# SubBus6.net
KiCad netlist of a schematic drawn in Altium Designer
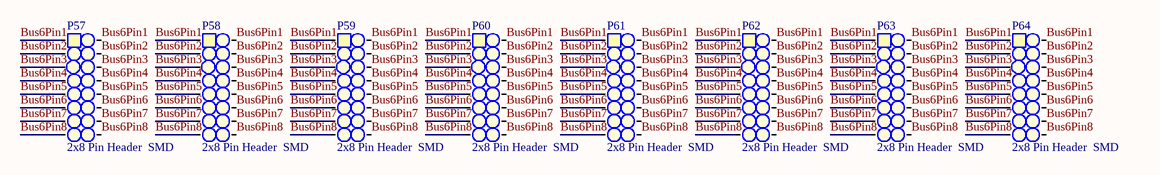
[diagram p0: SubBus6.SchDoc]

(export (version "E")
  (design (tool "Eeschema 10.0.6"))
  (components
    (comp (ref "P57")
      (value "2x8 Pin Header  SMD")
      (footprint "2X8_SMD_PH_2.54")
      (description "2.54mm, SMD")
      (libsource (lib "jclib") (part "2x8 Pin Header  SMD"))
    )
    (comp (ref "P58")
      (value "2x8 Pin Header  SMD")
      (footprint "2X8_SMD_PH_2.54")
      (description "2.54mm, SMD")
      (libsource (lib "jclib") (part "2x8 Pin Header  SMD"))
    )
    (comp (ref "P59")
      (value "2x8 Pin Header  SMD")
      (footprint "2X8_SMD_PH_2.54")
      (description "2.54mm, SMD")
      (libsource (lib "jclib") (part "2x8 Pin Header  SMD"))
    )
    (comp (ref "P60")
      (value "2x8 Pin Header  SMD")
      (footprint "2X8_SMD_PH_2.54")
      (description "2.54mm, SMD")
      (libsource (lib "jclib") (part "2x8 Pin Header  SMD"))
    )
    (comp (ref "P61")
      (value "2x8 Pin Header  SMD")
      (footprint "2X8_SMD_PH_2.54")
      (description "2.54mm, SMD")
      (libsource (lib "jclib") (part "2x8 Pin Header  SMD"))
    )
    (comp (ref "P62")
      (value "2x8 Pin Header  SMD")
      (footprint "2X8_SMD_PH_2.54")
      (description "2.54mm, SMD")
      (libsource (lib "jclib") (part "2x8 Pin Header  SMD"))
    )
    (comp (ref "P63")
      (value "2x8 Pin Header  SMD")
      (footprint "2X8_SMD_PH_2.54")
      (description "2.54mm, SMD")
      (libsource (lib "jclib") (part "2x8 Pin Header  SMD"))
    )
    (comp (ref "P64")
      (value "2x8 Pin Header  SMD")
      (footprint "2X8_SMD_PH_2.54")
      (description "2.54mm, SMD")
      (libsource (lib "jclib") (part "2x8 Pin Header  SMD"))
    )
  )
  (nets
    (net (code "1") (name "/Bus6Pin1") (class "Default")
      (node (ref "P57") (pin "1") (pinfunction "1_1") (pintype "passive"))
      (node (ref "P57") (pin "16") (pinfunction "16_16") (pintype "passive"))
      (node (ref "P58") (pin "1") (pinfunction "1_1") (pintype "passive"))
      (node (ref "P58") (pin "16") (pinfunction "16_16") (pintype "passive"))
      (node (ref "P59") (pin "1") (pinfunction "1_1") (pintype "passive"))
      (node (ref "P59") (pin "16") (pinfunction "16_16") (pintype "passive"))
      (node (ref "P60") (pin "1") (pinfunction "1_1") (pintype "passive"))
      (node (ref "P60") (pin "16") (pinfunction "16_16") (pintype "passive"))
      (node (ref "P61") (pin "1") (pinfunction "1_1") (pintype "passive"))
      (node (ref "P61") (pin "16") (pinfunction "16_16") (pintype "passive"))
      (node (ref "P62") (pin "1") (pinfunction "1_1") (pintype "passive"))
      (node (ref "P62") (pin "16") (pinfunction "16_16") (pintype "passive"))
      (node (ref "P63") (pin "1") (pinfunction "1_1") (pintype "passive"))
      (node (ref "P63") (pin "16") (pinfunction "16_16") (pintype "passive"))
      (node (ref "P64") (pin "1") (pinfunction "1_1") (pintype "passive"))
      (node (ref "P64") (pin "16") (pinfunction "16_16") (pintype "passive"))
    )
    (net (code "2") (name "/Bus6Pin2") (class "Default")
      (node (ref "P57") (pin "15") (pinfunction "15_15") (pintype "passive"))
      (node (ref "P57") (pin "2") (pinfunction "2_2") (pintype "passive"))
      (node (ref "P58") (pin "15") (pinfunction "15_15") (pintype "passive"))
      (node (ref "P58") (pin "2") (pinfunction "2_2") (pintype "passive"))
      (node (ref "P59") (pin "15") (pinfunction "15_15") (pintype "passive"))
      (node (ref "P59") (pin "2") (pinfunction "2_2") (pintype "passive"))
      (node (ref "P60") (pin "15") (pinfunction "15_15") (pintype "passive"))
      (node (ref "P60") (pin "2") (pinfunction "2_2") (pintype "passive"))
      (node (ref "P61") (pin "15") (pinfunction "15_15") (pintype "passive"))
      (node (ref "P61") (pin "2") (pinfunction "2_2") (pintype "passive"))
      (node (ref "P62") (pin "15") (pinfunction "15_15") (pintype "passive"))
      (node (ref "P62") (pin "2") (pinfunction "2_2") (pintype "passive"))
      (node (ref "P63") (pin "15") (pinfunction "15_15") (pintype "passive"))
      (node (ref "P63") (pin "2") (pinfunction "2_2") (pintype "passive"))
      (node (ref "P64") (pin "15") (pinfunction "15_15") (pintype "passive"))
      (node (ref "P64") (pin "2") (pinfunction "2_2") (pintype "passive"))
    )
    (net (code "3") (name "/Bus6Pin3") (class "Default")
      (node (ref "P57") (pin "14") (pinfunction "14_14") (pintype "passive"))
      (node (ref "P57") (pin "3") (pinfunction "3_3") (pintype "passive"))
      (node (ref "P58") (pin "14") (pinfunction "14_14") (pintype "passive"))
      (node (ref "P58") (pin "3") (pinfunction "3_3") (pintype "passive"))
      (node (ref "P59") (pin "14") (pinfunction "14_14") (pintype "passive"))
      (node (ref "P59") (pin "3") (pinfunction "3_3") (pintype "passive"))
      (node (ref "P60") (pin "14") (pinfunction "14_14") (pintype "passive"))
      (node (ref "P60") (pin "3") (pinfunction "3_3") (pintype "passive"))
      (node (ref "P61") (pin "14") (pinfunction "14_14") (pintype "passive"))
      (node (ref "P61") (pin "3") (pinfunction "3_3") (pintype "passive"))
      (node (ref "P62") (pin "14") (pinfunction "14_14") (pintype "passive"))
      (node (ref "P62") (pin "3") (pinfunction "3_3") (pintype "passive"))
      (node (ref "P63") (pin "14") (pinfunction "14_14") (pintype "passive"))
      (node (ref "P63") (pin "3") (pinfunction "3_3") (pintype "passive"))
      (node (ref "P64") (pin "14") (pinfunction "14_14") (pintype "passive"))
      (node (ref "P64") (pin "3") (pinfunction "3_3") (pintype "passive"))
    )
    (net (code "4") (name "/Bus6Pin4") (class "Default")
      (node (ref "P57") (pin "13") (pinfunction "13_13") (pintype "passive"))
      (node (ref "P57") (pin "4") (pinfunction "4_4") (pintype "passive"))
      (node (ref "P58") (pin "13") (pinfunction "13_13") (pintype "passive"))
      (node (ref "P58") (pin "4") (pinfunction "4_4") (pintype "passive"))
      (node (ref "P59") (pin "13") (pinfunction "13_13") (pintype "passive"))
      (node (ref "P59") (pin "4") (pinfunction "4_4") (pintype "passive"))
      (node (ref "P60") (pin "13") (pinfunction "13_13") (pintype "passive"))
      (node (ref "P60") (pin "4") (pinfunction "4_4") (pintype "passive"))
      (node (ref "P61") (pin "13") (pinfunction "13_13") (pintype "passive"))
      (node (ref "P61") (pin "4") (pinfunction "4_4") (pintype "passive"))
      (node (ref "P62") (pin "13") (pinfunction "13_13") (pintype "passive"))
      (node (ref "P62") (pin "4") (pinfunction "4_4") (pintype "passive"))
      (node (ref "P63") (pin "13") (pinfunction "13_13") (pintype "passive"))
      (node (ref "P63") (pin "4") (pinfunction "4_4") (pintype "passive"))
      (node (ref "P64") (pin "13") (pinfunction "13_13") (pintype "passive"))
      (node (ref "P64") (pin "4") (pinfunction "4_4") (pintype "passive"))
    )
    (net (code "5") (name "/Bus6Pin5") (class "Default")
      (node (ref "P57") (pin "12") (pinfunction "12_12") (pintype "passive"))
      (node (ref "P57") (pin "5") (pinfunction "5_5") (pintype "passive"))
      (node (ref "P58") (pin "12") (pinfunction "12_12") (pintype "passive"))
      (node (ref "P58") (pin "5") (pinfunction "5_5") (pintype "passive"))
      (node (ref "P59") (pin "12") (pinfunction "12_12") (pintype "passive"))
      (node (ref "P59") (pin "5") (pinfunction "5_5") (pintype "passive"))
      (node (ref "P60") (pin "12") (pinfunction "12_12") (pintype "passive"))
      (node (ref "P60") (pin "5") (pinfunction "5_5") (pintype "passive"))
      (node (ref "P61") (pin "12") (pinfunction "12_12") (pintype "passive"))
      (node (ref "P61") (pin "5") (pinfunction "5_5") (pintype "passive"))
      (node (ref "P62") (pin "12") (pinfunction "12_12") (pintype "passive"))
      (node (ref "P62") (pin "5") (pinfunction "5_5") (pintype "passive"))
      (node (ref "P63") (pin "12") (pinfunction "12_12") (pintype "passive"))
      (node (ref "P63") (pin "5") (pinfunction "5_5") (pintype "passive"))
      (node (ref "P64") (pin "12") (pinfunction "12_12") (pintype "passive"))
      (node (ref "P64") (pin "5") (pinfunction "5_5") (pintype "passive"))
    )
    (net (code "6") (name "/Bus6Pin6") (class "Default")
      (node (ref "P57") (pin "11") (pinfunction "11_11") (pintype "passive"))
      (node (ref "P57") (pin "6") (pinfunction "6_6") (pintype "passive"))
      (node (ref "P58") (pin "11") (pinfunction "11_11") (pintype "passive"))
      (node (ref "P58") (pin "6") (pinfunction "6_6") (pintype "passive"))
      (node (ref "P59") (pin "11") (pinfunction "11_11") (pintype "passive"))
      (node (ref "P59") (pin "6") (pinfunction "6_6") (pintype "passive"))
      (node (ref "P60") (pin "11") (pinfunction "11_11") (pintype "passive"))
      (node (ref "P60") (pin "6") (pinfunction "6_6") (pintype "passive"))
      (node (ref "P61") (pin "11") (pinfunction "11_11") (pintype "passive"))
      (node (ref "P61") (pin "6") (pinfunction "6_6") (pintype "passive"))
      (node (ref "P62") (pin "11") (pinfunction "11_11") (pintype "passive"))
      (node (ref "P62") (pin "6") (pinfunction "6_6") (pintype "passive"))
      (node (ref "P63") (pin "11") (pinfunction "11_11") (pintype "passive"))
      (node (ref "P63") (pin "6") (pinfunction "6_6") (pintype "passive"))
      (node (ref "P64") (pin "11") (pinfunction "11_11") (pintype "passive"))
      (node (ref "P64") (pin "6") (pinfunction "6_6") (pintype "passive"))
    )
    (net (code "7") (name "/Bus6Pin7") (class "Default")
      (node (ref "P57") (pin "10") (pinfunction "10_10") (pintype "passive"))
      (node (ref "P57") (pin "7") (pinfunction "7_7") (pintype "passive"))
      (node (ref "P58") (pin "10") (pinfunction "10_10") (pintype "passive"))
      (node (ref "P58") (pin "7") (pinfunction "7_7") (pintype "passive"))
      (node (ref "P59") (pin "10") (pinfunction "10_10") (pintype "passive"))
      (node (ref "P59") (pin "7") (pinfunction "7_7") (pintype "passive"))
      (node (ref "P60") (pin "10") (pinfunction "10_10") (pintype "passive"))
      (node (ref "P60") (pin "7") (pinfunction "7_7") (pintype "passive"))
      (node (ref "P61") (pin "10") (pinfunction "10_10") (pintype "passive"))
      (node (ref "P61") (pin "7") (pinfunction "7_7") (pintype "passive"))
      (node (ref "P62") (pin "10") (pinfunction "10_10") (pintype "passive"))
      (node (ref "P62") (pin "7") (pinfunction "7_7") (pintype "passive"))
      (node (ref "P63") (pin "10") (pinfunction "10_10") (pintype "passive"))
      (node (ref "P63") (pin "7") (pinfunction "7_7") (pintype "passive"))
      (node (ref "P64") (pin "10") (pinfunction "10_10") (pintype "passive"))
      (node (ref "P64") (pin "7") (pinfunction "7_7") (pintype "passive"))
    )
    (net (code "8") (name "/Bus6Pin8") (class "Default")
      (node (ref "P57") (pin "8") (pinfunction "8_8") (pintype "passive"))
      (node (ref "P57") (pin "9") (pinfunction "9_9") (pintype "passive"))
      (node (ref "P58") (pin "8") (pinfunction "8_8") (pintype "passive"))
      (node (ref "P58") (pin "9") (pinfunction "9_9") (pintype "passive"))
      (node (ref "P59") (pin "8") (pinfunction "8_8") (pintype "passive"))
      (node (ref "P59") (pin "9") (pinfunction "9_9") (pintype "passive"))
      (node (ref "P60") (pin "8") (pinfunction "8_8") (pintype "passive"))
      (node (ref "P60") (pin "9") (pinfunction "9_9") (pintype "passive"))
      (node (ref "P61") (pin "8") (pinfunction "8_8") (pintype "passive"))
      (node (ref "P61") (pin "9") (pinfunction "9_9") (pintype "passive"))
      (node (ref "P62") (pin "8") (pinfunction "8_8") (pintype "passive"))
      (node (ref "P62") (pin "9") (pinfunction "9_9") (pintype "passive"))
      (node (ref "P63") (pin "8") (pinfunction "8_8") (pintype "passive"))
      (node (ref "P63") (pin "9") (pinfunction "9_9") (pintype "passive"))
      (node (ref "P64") (pin "8") (pinfunction "8_8") (pintype "passive"))
      (node (ref "P64") (pin "9") (pinfunction "9_9") (pintype "passive"))
    )
  )
)
